# High_freq.net
KiCad netlist of a schematic drawn in Altium Designer
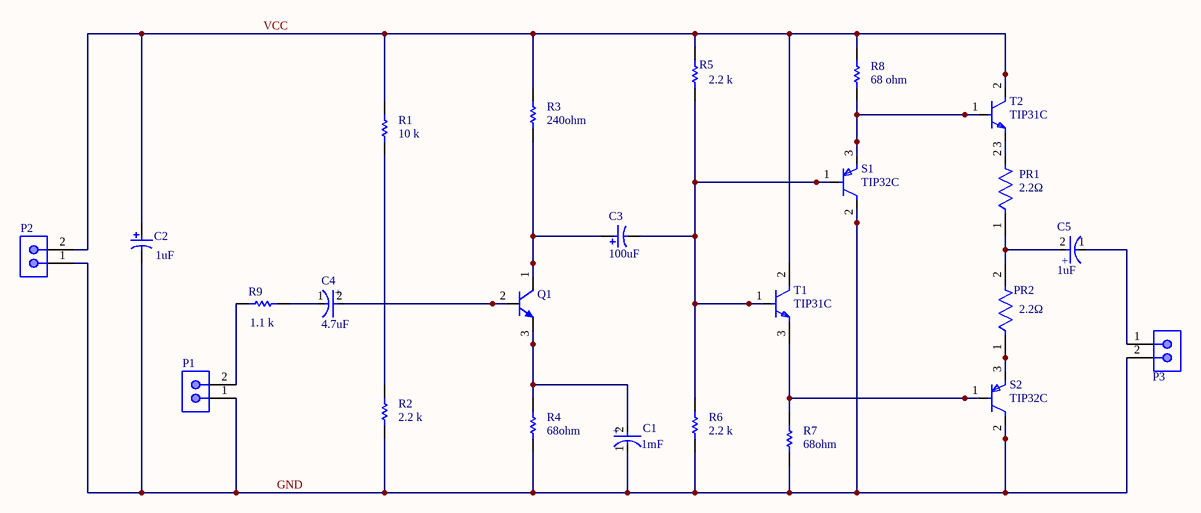
[diagram p0: High_freq.SchDoc]

(export (version "E")
  (design (tool "Eeschema 10.0.6"))
  (components
    (comp (ref "C1")
      (value "EEUFK1C102")
      (footprint "FP-RAD-TH-D_10_0_5-L_16_1-MFG")
      (description "Aluminum Electrolytic Capacitors (Radial Lead Type) AEC-Q200 Qualified 1000uF ±20% 16V")
      (fields
        (field (name "CAPACITANCE") "1mF")
        (field (name "VOLTAGE") "16V")
        (field (name "TOLERANCE") "20%")
      )
      (libsource (lib "Altium Content Vault") (part "a00bbbee19879c290e62620ae7e47b1"))
    )
    (comp (ref "C2")
      (value "ECA-1VM101")
      (footprint "CAPPR55-250-1120X630X1220")
      (fields (field (name "MANUFACTURER") "Panasonic") (field (name "CAP") "1uF"))
      (libsource (lib "Altium Content Vault") (part "CAP-P-2"))
    )
    (comp (ref "C3")
      (value "ECA-1VM101")
      (footprint "CAPPR55-250-1120X630X1220")
      (fields (field (name "MANUFACTURER") "Panasonic") (field (name "CAP") "100uF"))
      (libsource (lib "Altium Content Vault") (part "CAP-P-2"))
    )
    (comp (ref "C4")
      (value "EEAGA1A470")
      (footprint "FP-RAD-TH-D_6_3_0_5-L_7_1-MFG")
      (description "Aluminum Electrolytic Capacitors (Radial Lead Type) 47uF ±20% 10V")
      (fields
        (field (name "CAPACITANCE") "4.7uF")
        (field (name "VOLTAGE") "10V")
        (field (name "TOLERANCE") "20%")
      )
      (libsource (lib "Altium Content Vault") (part "a00bbbee19879c290e62620ae7e47b1"))
    )
    (comp (ref "C5")
      (value "EEAGA1A470")
      (footprint "FP-RAD-TH-D_6_3_0_5-L_7_1-MFG")
      (description "Aluminum Electrolytic Capacitors (Radial Lead Type) 47uF ±20% 10V")
      (fields
        (field (name "CAPACITANCE") "1uF")
        (field (name "VOLTAGE") "10V")
        (field (name "TOLERANCE") "20%")
      )
      (libsource (lib "Altium Content Vault") (part "a00bbbee19879c290e62620ae7e47b1"))
    )
    (comp (ref "P1")
      (value "22-27-2021")
      (footprint "MOLX-22-27-2021_V")
      (fields (field (name "MANUFACTURER") "Molex") (field (name "PARTNUMBER") "0022272021"))
      (libsource (lib "") (part "CN-1P-M-R2_1"))
    )
    (comp (ref "P2")
      (value "22-27-2021")
      (footprint "MOLX-22-27-2021_V")
      (fields (field (name "MANUFACTURER") "Molex") (field (name "PARTNUMBER") "0022272021"))
      (libsource (lib "") (part "CN-1P-M-R2_1"))
    )
    (comp (ref "P3")
      (value "22-27-2021")
      (footprint "MOLX-22-27-2021_V")
      (fields (field (name "MANUFACTURER") "Molex") (field (name "PARTNUMBER") "0022272021"))
      (libsource (lib "Altium Content Vault") (part "CN-1P-M-R2"))
    )
    (comp (ref "PR1")
      (value "SQP500JB-1R2")
      (footprint "FP-SQP500-MFG")
      (description "RES 1.2 OHM 5W 5% AXIAL")
      (fields
        (field (name "RESISTANCE") "2.2Ω")
        (field (name "OCTOPART") "https://octopart.com/sqp500jb-1r2-yageo-1162571")
        (field (name "MANUFACTURER") "Yageo")
      )
      (libsource (lib "Altium Content Vault") (part "1029c3af85768c4190bb7ad29bc67b5"))
    )
    (comp (ref "PR2")
      (value "SQP500JB-1R2")
      (footprint "FP-SQP500-MFG")
      (description "RES 1.2 OHM 5W 5% AXIAL")
      (fields
        (field (name "RESISTANCE") "2.2Ω")
        (field (name "OCTOPART") "https://octopart.com/sqp500jb-1r2-yageo-1162571")
        (field (name "MANUFACTURER") "Yageo")
      )
      (libsource (lib "Altium Content Vault") (part "1029c3af85768c4190bb7ad29bc67b5"))
    )
    (comp (ref "Q1")
      (value "BC547BRL1G")
      (footprint "ONSC-TO-92-3-29-11_AM_BL")
      (description "Amplifier Transistor, NPN Silicon, 3-Pin TO-92, Pb-Free, Tape and Reel")
      (fields (field (name "MANUFACTURER") "On Semiconductor"))
      (libsource (lib "Altium Content Vault") (part "ONSC-NPN-C1B2E3-3"))
    )
    (comp (ref "R1")
      (value "MFR-25FBF52-1K")
      (footprint "RESA60-630X240")
      (description "Axial Resistor, 1 KOhm, +/- 1%, 250 mW, -55 to 155 degC, 2-Pin THD, RoHS, Bulk")
      (fields (field (name "TOLERANCE") "1%") (field (name "RESISTANCE") "10 k"))
      (libsource (lib "Altium Content Vault") (part "RES-2"))
    )
    (comp (ref "R2")
      (value "MFR-25FBF52-1K")
      (footprint "RESA60-630X240")
      (description "Axial Resistor, 1 KOhm, +/- 1%, 250 mW, -55 to 155 degC, 2-Pin THD, RoHS, Bulk")
      (fields (field (name "TOLERANCE") "1%") (field (name "RESISTANCE") "2.2 k"))
      (libsource (lib "Altium Content Vault") (part "RES-2"))
    )
    (comp (ref "R3")
      (value "MFR-25FBF52-1K")
      (footprint "RESA60-630X240")
      (description "Axial Resistor, 1 KOhm, +/- 1%, 250 mW, -55 to 155 degC, 2-Pin THD, RoHS, Bulk")
      (fields (field (name "TOLERANCE") "1%") (field (name "RESISTANCE") "240ohm"))
      (libsource (lib "Altium Content Vault") (part "RES-2"))
    )
    (comp (ref "R4")
      (value "MFR-25FBF52-1K")
      (footprint "RESA60-630X240")
      (description "Axial Resistor, 1 KOhm, +/- 1%, 250 mW, -55 to 155 degC, 2-Pin THD, RoHS, Bulk")
      (fields (field (name "TOLERANCE") "1%") (field (name "RESISTANCE") "68ohm"))
      (libsource (lib "Altium Content Vault") (part "RES-2"))
    )
    (comp (ref "R5")
      (value "MFR-25FBF52-1K")
      (footprint "RESA60-630X240")
      (description "Axial Resistor, 1 KOhm, +/- 1%, 250 mW, -55 to 155 degC, 2-Pin THD, RoHS, Bulk")
      (fields (field (name "TOLERANCE") "1%") (field (name "RESISTANCE") "2.2 k"))
      (libsource (lib "Altium Content Vault") (part "RES-2"))
    )
    (comp (ref "R6")
      (value "MFR-25FBF52-1K")
      (footprint "RESA60-630X240")
      (description "Axial Resistor, 1 KOhm, +/- 1%, 250 mW, -55 to 155 degC, 2-Pin THD, RoHS, Bulk")
      (fields (field (name "TOLERANCE") "1%") (field (name "RESISTANCE") "2.2 k"))
      (libsource (lib "Altium Content Vault") (part "RES-2"))
    )
    (comp (ref "R7")
      (value "MFR-25FBF52-1K")
      (footprint "RESA60-630X240")
      (description "Axial Resistor, 1 KOhm, +/- 1%, 250 mW, -55 to 155 degC, 2-Pin THD, RoHS, Bulk")
      (fields (field (name "TOLERANCE") "1%") (field (name "RESISTANCE") "68ohm"))
      (libsource (lib "Altium Content Vault") (part "RES-2"))
    )
    (comp (ref "R8")
      (value "MFR-25FBF52-1K")
      (footprint "RESA60-630X240")
      (description "Axial Resistor, 1 KOhm, +/- 1%, 250 mW, -55 to 155 degC, 2-Pin THD, RoHS, Bulk")
      (fields (field (name "TOLERANCE") "1%") (field (name "RESISTANCE") "68 ohm"))
      (libsource (lib "Altium Content Vault") (part "RES-2"))
    )
    (comp (ref "R9")
      (value "MFR-25FBF52-1K")
      (footprint "RESA60-630X240")
      (description "Axial Resistor, 1 KOhm, +/- 1%, 250 mW, -55 to 155 degC, 2-Pin THD, RoHS, Bulk")
      (fields (field (name "TOLERANCE") "1%") (field (name "RESISTANCE") "1.1 k"))
      (libsource (lib "Altium Content Vault") (part "RES-2"))
    )
    (comp (ref "S1")
      (value "TIP32C")
      (footprint "FP-TO-220-P0A0015988-MFG")
      (description "TRANS PNP 100V 3A TO-220")
      (fields
        (field (name "MANUFACTURER") "STMicroelectronics")
        (field (name "OCTOPART") "https://octopart.com/tip32c-stmicroelectronics-353617")
      )
      (libsource (lib "Altium Content Vault") (part "802a31d42ca070764d097f06bc9597f"))
    )
    (comp (ref "S2")
      (value "TIP32C")
      (footprint "FP-TO-220-P0A0015988-MFG")
      (description "TRANS PNP 100V 3A TO-220")
      (fields
        (field (name "MANUFACTURER") "STMicroelectronics")
        (field (name "OCTOPART") "https://octopart.com/tip32c-stmicroelectronics-353617")
      )
      (libsource (lib "Altium Content Vault") (part "802a31d42ca070764d097f06bc9597f"))
    )
    (comp (ref "T1")
      (value "TIP31C")
      (footprint "FP-TO-220-P0A0015988-MFG")
      (description "TRANS NPN 100V 3A TO-220")
      (fields
        (field (name "OCTOPART") "https://octopart.com/tip31c-stmicroelectronics-15555")
        (field (name "MANUFACTURER") "STMicroelectronics")
      )
      (libsource (lib "Altium Content Vault") (part "1c57d9dae74fe2702546667b0e849db"))
    )
    (comp (ref "T2")
      (value "TIP31C")
      (footprint "FP-TO-220-P0A0015988-MFG")
      (description "TRANS NPN 100V 3A TO-220")
      (fields
        (field (name "OCTOPART") "https://octopart.com/tip31c-stmicroelectronics-15555")
        (field (name "MANUFACTURER") "STMicroelectronics")
      )
      (libsource (lib "Altium Content Vault") (part "1c57d9dae74fe2702546667b0e849db"))
    )
  )
  (nets
    (net (code "1") (name "/GND") (class "Default")
      (node (ref "C1") (pin "1") (pinfunction "C_1") (pintype "passive"))
      (node (ref "C2") (pin "2") (pinfunction "2_2") (pintype "passive"))
      (node (ref "P1") (pin "1") (pinfunction "1_1") (pintype "passive"))
      (node (ref "P2") (pin "1") (pinfunction "1_1") (pintype "passive"))
      (node (ref "P3") (pin "2") (pinfunction "2_2") (pintype "passive"))
      (node (ref "R2") (pin "1") (pinfunction "1_1") (pintype "passive"))
      (node (ref "R4") (pin "1") (pinfunction "1_1") (pintype "passive"))
      (node (ref "R6") (pin "1") (pinfunction "1_1") (pintype "passive"))
      (node (ref "R7") (pin "1") (pinfunction "1_1") (pintype "passive"))
      (node (ref "S1") (pin "2") (pinfunction "C_2") (pintype "passive"))
      (node (ref "S2") (pin "2") (pinfunction "C_2") (pintype "passive"))
    )
    (net (code "2") (name "/VCC") (class "Default")
      (node (ref "C2") (pin "1") (pinfunction "1_1") (pintype "passive"))
      (node (ref "P2") (pin "2") (pinfunction "2_2") (pintype "passive"))
      (node (ref "R1") (pin "2") (pinfunction "2_2") (pintype "passive"))
      (node (ref "R3") (pin "2") (pinfunction "2_2") (pintype "passive"))
      (node (ref "R5") (pin "2") (pinfunction "2_2") (pintype "passive"))
      (node (ref "R8") (pin "2") (pinfunction "2_2") (pintype "passive"))
      (node (ref "T1") (pin "2") (pinfunction "C_2") (pintype "passive"))
      (node (ref "T2") (pin "2") (pinfunction "C_2") (pintype "passive"))
    )
    (net (code "3") (name "Net-(C1-A)") (class "Default")
      (node (ref "C1") (pin "2") (pinfunction "A_2") (pintype "passive"))
      (node (ref "Q1") (pin "3") (pinfunction "E_3") (pintype "passive"))
      (node (ref "R4") (pin "2") (pinfunction "2_2") (pintype "passive"))
    )
    (net (code "4") (name "Net-(C4-A)") (class "Default")
      (node (ref "C4") (pin "2") (pinfunction "A_2") (pintype "passive"))
      (node (ref "Q1") (pin "2") (pinfunction "B_2") (pintype "passive"))
    )
    (net (code "5") (name "Net-(C4-C)") (class "Default")
      (node (ref "C4") (pin "1") (pinfunction "C_1") (pintype "passive"))
      (node (ref "R9") (pin "1") (pinfunction "1_1") (pintype "passive"))
    )
    (net (code "6") (name "Net-(C5-A)") (class "Default")
      (node (ref "C5") (pin "2") (pinfunction "A_2") (pintype "passive"))
      (node (ref "PR1") (pin "1") (pinfunction "1_1") (pintype "passive"))
      (node (ref "PR2") (pin "2") (pinfunction "2_2") (pintype "passive"))
    )
    (net (code "7") (name "Net-(C5-C)") (class "Default")
      (node (ref "C5") (pin "1") (pinfunction "C_1") (pintype "passive"))
      (node (ref "P3") (pin "1") (pinfunction "1_1") (pintype "passive"))
    )
    (net (code "8") (name "Net-(P1-Pad2)") (class "Default")
      (node (ref "P1") (pin "2") (pinfunction "2_2") (pintype "passive"))
      (node (ref "R9") (pin "2") (pinfunction "2_2") (pintype "passive"))
    )
    (net (code "9") (name "Net-(Q1-C)") (class "Default")
      (node (ref "C3") (pin "1") (pinfunction "1_1") (pintype "passive"))
      (node (ref "Q1") (pin "1") (pinfunction "C_1") (pintype "passive"))
      (node (ref "R3") (pin "1") (pinfunction "1_1") (pintype "passive"))
    )
    (net (code "10") (name "Net-(R1-Pad1)") (class "Default")
      (node (ref "R1") (pin "1") (pinfunction "1_1") (pintype "passive"))
      (node (ref "R2") (pin "2") (pinfunction "2_2") (pintype "passive"))
    )
    (net (code "11") (name "Net-(S1-B)") (class "Default")
      (node (ref "C3") (pin "2") (pinfunction "2_2") (pintype "passive"))
      (node (ref "R5") (pin "1") (pinfunction "1_1") (pintype "passive"))
      (node (ref "R6") (pin "2") (pinfunction "2_2") (pintype "passive"))
      (node (ref "S1") (pin "1") (pinfunction "B_1") (pintype "passive"))
      (node (ref "T1") (pin "1") (pinfunction "B_1") (pintype "passive"))
    )
    (net (code "12") (name "Net-(S1-E)") (class "Default")
      (node (ref "R8") (pin "1") (pinfunction "1_1") (pintype "passive"))
      (node (ref "S1") (pin "3") (pinfunction "E_3") (pintype "passive"))
      (node (ref "T2") (pin "1") (pinfunction "B_1") (pintype "passive"))
    )
    (net (code "13") (name "Net-(S2-B)") (class "Default")
      (node (ref "R7") (pin "2") (pinfunction "2_2") (pintype "passive"))
      (node (ref "S2") (pin "1") (pinfunction "B_1") (pintype "passive"))
      (node (ref "T1") (pin "3") (pinfunction "E_3") (pintype "passive"))
    )
    (net (code "14") (name "Net-(S2-E)") (class "Default")
      (node (ref "PR2") (pin "1") (pinfunction "1_1") (pintype "passive"))
      (node (ref "S2") (pin "3") (pinfunction "E_3") (pintype "passive"))
    )
    (net (code "15") (name "Net-(T2-E)") (class "Default")
      (node (ref "PR1") (pin "2") (pinfunction "2_2") (pintype "passive"))
      (node (ref "T2") (pin "3") (pinfunction "E_3") (pintype "passive"))
    )
  )
)
